# CPU_Board.net
KiCad netlist of a schematic drawn in Altium Designer
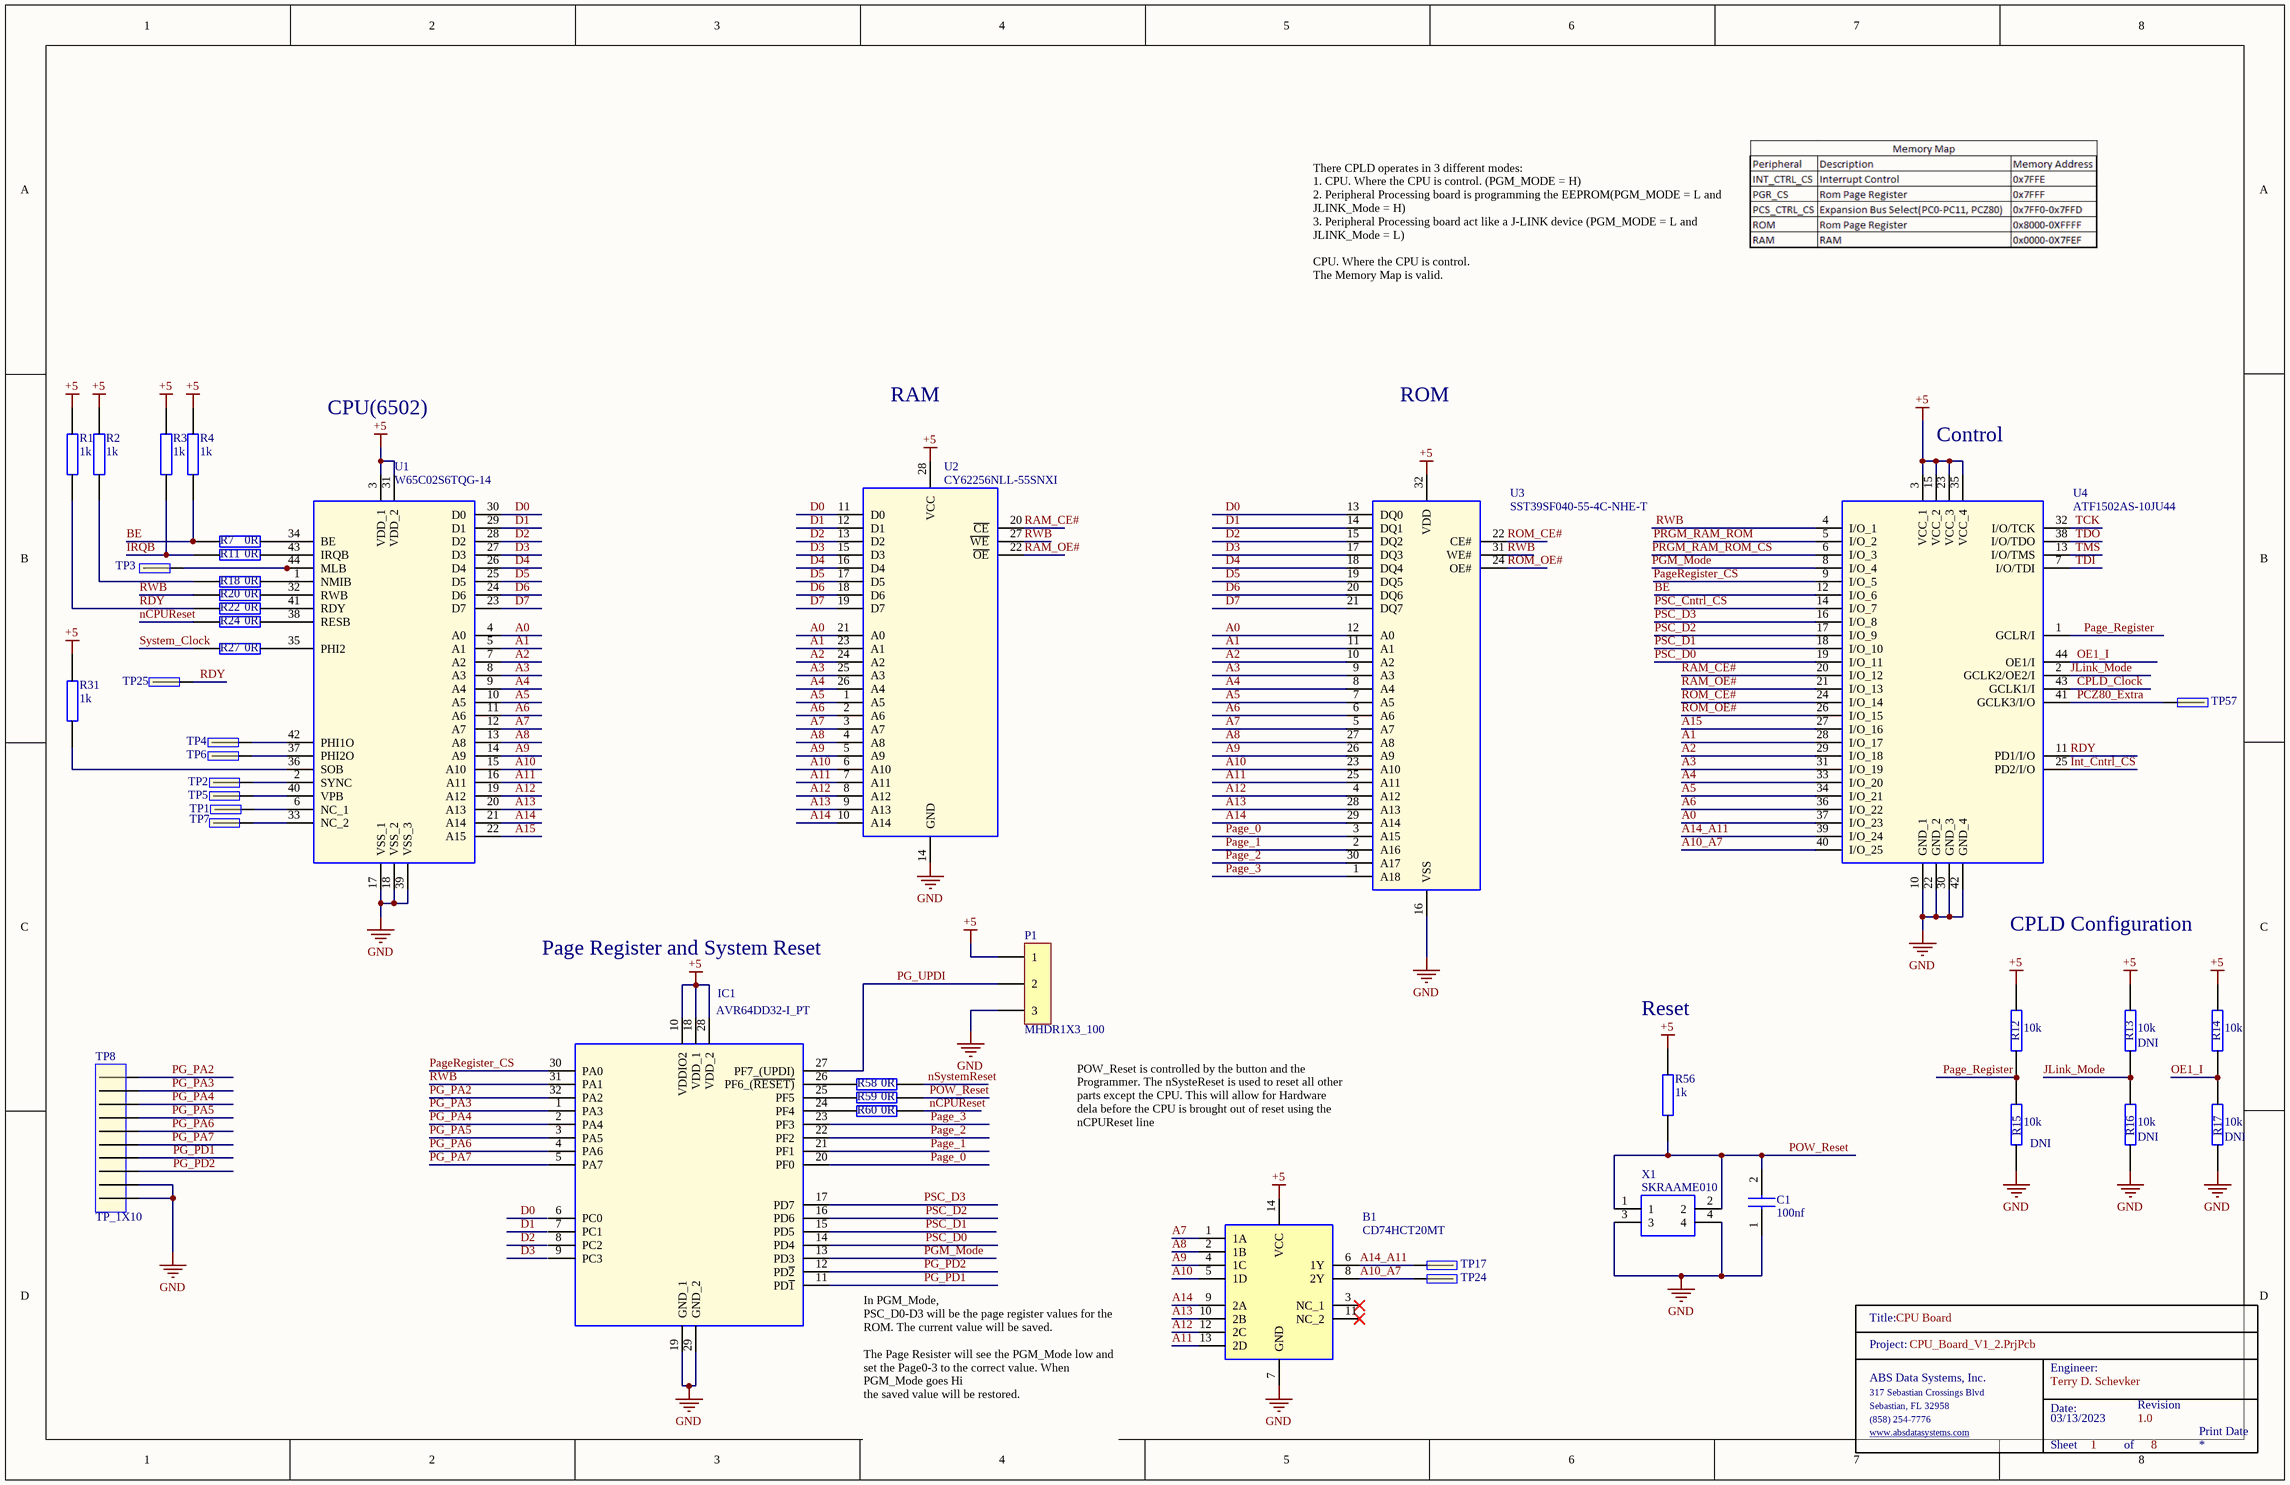
[diagram p0: CPU_Board.SchDoc]

(export (version "E")
  (design (tool "Eeschema 10.0.6"))
  (components
    (comp (ref "B1")
      (value "CD74HCT20MT")
      (footprint "SOIC127P600X175-14N")
      (description "Texas Instruments CD74HCT20MT, Dual 4-Input NAND Logic Gate, 14-Pin SOIC")
      (fields (field (name "MOUSER PART NUMBER") "595-CD74HCT20MT"))
      (libsource (lib "Logic") (part "CD74HCT20MT"))
    )
    (comp (ref "C1")
      (value "100nf")
      (footprint "0603")
      (description "Samsung Electro-Mechanics 0603 100nf")
      (libsource (lib "Capacitors") (part "CL10B104JB8NNNC"))
    )
    (comp (ref "IC1")
      (value "AVR64DD32-I_PT")
      (footprint "CPU_Memory:QFP80P900X900X120-32N")
      (description "Integrated Circuit")
      (fields (field (name "MANUFACTURER_PART_NUMBER") "AVR64DD32-I/PT ¦ MULTI-VOLTAGE I/O"))
      (libsource (lib "CPU_Memory") (part "AVR64DD32-I_PT"))
    )
    (comp (ref "P1")
      (value "MHDR1X3_100")
      (footprint "MHDR1X3_100")
      (description "Header, 3-Pin")
      (fields (field (name "PUBLISHER") "Altium Limited"))
      (libsource (lib "Connectors") (part "MHDR1X3_100"))
    )
    (comp (ref "R1")
      (value "1k")
      (footprint "0603")
      (description "YAGEO 0603 1k ohm")
      (fields
        (field (name "MOUSER PART NUMBER") "603-RC0603JR-070RL")
        (field (name "MANUFACTURER_PART_NUMBER") "RC0603JR-070RL")
      )
      (libsource (lib "Resistors") (part "AC0603FR-7W1KL"))
    )
    (comp (ref "R2")
      (value "1k")
      (footprint "0603")
      (description "YAGEO 0603 1k ohm")
      (fields
        (field (name "MOUSER PART NUMBER") "603-RC0603JR-070RL")
        (field (name "MANUFACTURER_PART_NUMBER") "RC0603JR-070RL")
      )
      (libsource (lib "Resistors") (part "AC0603FR-7W1KL"))
    )
    (comp (ref "R3")
      (value "1k")
      (footprint "0603")
      (description "YAGEO 0603 1k ohm")
      (fields
        (field (name "MOUSER PART NUMBER") "603-RC0603JR-070RL")
        (field (name "MANUFACTURER_PART_NUMBER") "RC0603JR-070RL")
      )
      (libsource (lib "Resistors") (part "AC0603FR-7W1KL"))
    )
    (comp (ref "R4")
      (value "1k")
      (footprint "0603")
      (description "YAGEO 0603 1k ohm")
      (fields
        (field (name "MOUSER PART NUMBER") "603-RC0603JR-070RL")
        (field (name "MANUFACTURER_PART_NUMBER") "RC0603JR-070RL")
      )
      (libsource (lib "Resistors") (part "AC0603FR-7W1KL"))
    )
    (comp (ref "R7")
      (value "0R")
      (footprint "0603")
      (description "YAGEO 0603 0 ohm")
      (fields
        (field (name "MOUSER PART NUMBER") "603-RC0603JR-070RL")
        (field (name "MANUFACTURER_PART_NUMBER") "RC0603JR-070RL")
      )
      (libsource (lib "Resistors") (part "RC0603JR-070RL"))
    )
    (comp (ref "R11")
      (value "0R")
      (footprint "0603")
      (description "YAGEO 0603 0 ohm")
      (fields
        (field (name "MOUSER PART NUMBER") "603-RC0603JR-070RL")
        (field (name "MANUFACTURER_PART_NUMBER") "RC0603JR-070RL")
      )
      (libsource (lib "Resistors") (part "RC0603JR-070RL"))
    )
    (comp (ref "R12")
      (value "10k")
      (footprint "0603")
      (description "YAGEO 0603 10k ohm")
      (fields
        (field (name "MOUSER PART NUMBER") "603-RC0603JR-070RL")
        (field (name "MANUFACTURER_PART_NUMBER") "RC0603JR-070RL")
      )
      (libsource (lib "Resistors") (part "RC0603JR-0710KL"))
    )
    (comp (ref "R13")
      (value "10k")
      (footprint "0603")
      (description "YAGEO 0603 10k ohm")
      (fields
        (field (name "MOUSER PART NUMBER") "603-RC0603JR-070RL")
        (field (name "MANUFACTURER_PART_NUMBER") "RC0603JR-070RL")
      )
      (libsource (lib "Resistors") (part "RC0603JR-0710KL"))
    )
    (comp (ref "R14")
      (value "10k")
      (footprint "0603")
      (description "YAGEO 0603 10k ohm")
      (fields
        (field (name "MOUSER PART NUMBER") "603-RC0603JR-070RL")
        (field (name "MANUFACTURER_PART_NUMBER") "RC0603JR-070RL")
      )
      (libsource (lib "Resistors") (part "RC0603JR-0710KL"))
    )
    (comp (ref "R15")
      (value "10k")
      (footprint "0603")
      (description "YAGEO 0603 10k ohm")
      (fields
        (field (name "MOUSER PART NUMBER") "603-RC0603JR-070RL")
        (field (name "MANUFACTURER_PART_NUMBER") "RC0603JR-070RL")
      )
      (libsource (lib "Resistors") (part "RC0603JR-0710KL"))
    )
    (comp (ref "R16")
      (value "10k")
      (footprint "0603")
      (description "YAGEO 0603 10k ohm")
      (fields
        (field (name "MOUSER PART NUMBER") "603-RC0603JR-070RL")
        (field (name "MANUFACTURER_PART_NUMBER") "RC0603JR-070RL")
      )
      (libsource (lib "Resistors") (part "RC0603JR-0710KL"))
    )
    (comp (ref "R17")
      (value "10k")
      (footprint "0603")
      (description "YAGEO 0603 10k ohm")
      (fields
        (field (name "MOUSER PART NUMBER") "603-RC0603JR-070RL")
        (field (name "MANUFACTURER_PART_NUMBER") "RC0603JR-070RL")
      )
      (libsource (lib "Resistors") (part "RC0603JR-0710KL"))
    )
    (comp (ref "R18")
      (value "0R")
      (footprint "0603")
      (description "YAGEO 0603 0 ohm")
      (fields
        (field (name "MOUSER PART NUMBER") "603-RC0603JR-070RL")
        (field (name "MANUFACTURER_PART_NUMBER") "RC0603JR-070RL")
      )
      (libsource (lib "Resistors") (part "RC0603JR-070RL"))
    )
    (comp (ref "R20")
      (value "0R")
      (footprint "0603")
      (description "YAGEO 0603 0 ohm")
      (fields
        (field (name "MOUSER PART NUMBER") "603-RC0603JR-070RL")
        (field (name "MANUFACTURER_PART_NUMBER") "RC0603JR-070RL")
      )
      (libsource (lib "Resistors") (part "RC0603JR-070RL"))
    )
    (comp (ref "R22")
      (value "0R")
      (footprint "0603")
      (description "YAGEO 0603 0 ohm")
      (fields
        (field (name "MOUSER PART NUMBER") "603-RC0603JR-070RL")
        (field (name "MANUFACTURER_PART_NUMBER") "RC0603JR-070RL")
      )
      (libsource (lib "Resistors") (part "RC0603JR-070RL"))
    )
    (comp (ref "R24")
      (value "0R")
      (footprint "0603")
      (description "YAGEO 0603 0 ohm")
      (fields
        (field (name "MOUSER PART NUMBER") "603-RC0603JR-070RL")
        (field (name "MANUFACTURER_PART_NUMBER") "RC0603JR-070RL")
      )
      (libsource (lib "Resistors") (part "RC0603JR-070RL"))
    )
    (comp (ref "R27")
      (value "0R")
      (footprint "0603")
      (description "YAGEO 0603 0 ohm")
      (fields
        (field (name "MOUSER PART NUMBER") "603-RC0603JR-070RL")
        (field (name "MANUFACTURER_PART_NUMBER") "RC0603JR-070RL")
      )
      (libsource (lib "Resistors") (part "RC0603JR-070RL"))
    )
    (comp (ref "R31")
      (value "1k")
      (footprint "Capacitors:0603")
      (description "YAGEO 0603 1k ohm")
      (fields
        (field (name "MOUSER PART NUMBER") "603-RC0603JR-070RL")
        (field (name "MANUFACTURER_PART_NUMBER") "RC0603JR-070RL")
      )
      (libsource (lib "Resistors") (part "AC0603FR-7W1KL"))
    )
    (comp (ref "R56")
      (value "1k")
      (footprint "0603")
      (description "YAGEO 0603 1k ohm")
      (fields
        (field (name "MOUSER PART NUMBER") "603-RC0603JR-070RL")
        (field (name "MANUFACTURER_PART_NUMBER") "RC0603JR-070RL")
      )
      (libsource (lib "Resistors") (part "AC0603FR-7W1KL"))
    )
    (comp (ref "R58")
      (value "0R")
      (footprint "Capacitors:0603")
      (description "YAGEO 0603 0 ohm")
      (fields
        (field (name "MOUSER PART NUMBER") "603-RC0603JR-070RL")
        (field (name "MANUFACTURER_PART_NUMBER") "RC0603JR-070RL")
      )
      (libsource (lib "Resistors") (part "RC0603JR-070RL"))
    )
    (comp (ref "R59")
      (value "0R")
      (footprint "0603")
      (description "YAGEO 0603 0 ohm")
      (fields
        (field (name "MOUSER PART NUMBER") "603-RC0603JR-070RL")
        (field (name "MANUFACTURER_PART_NUMBER") "RC0603JR-070RL")
      )
      (libsource (lib "Resistors") (part "RC0603JR-070RL"))
    )
    (comp (ref "R60")
      (value "0R")
      (footprint "0603")
      (description "YAGEO 0603 0 ohm")
      (fields
        (field (name "MOUSER PART NUMBER") "603-RC0603JR-070RL")
        (field (name "MANUFACTURER_PART_NUMBER") "RC0603JR-070RL")
      )
      (libsource (lib "Resistors") (part "RC0603JR-070RL"))
    )
    (comp (ref "TitleBlock_1") (value "TitleBlock") (libsource (lib "Misc") (part "TitleBlock")))
    (comp (ref "TP1")
      (value "TP")
      (footprint "TP")
      (fields
        (field (name "MANUFACTURER") "Samtec")
        (field (name "MANUFACTURER PART NUMBER") "TST-105-01-G-D")
      )
      (libsource (lib "Misc") (part "TP"))
    )
    (comp (ref "TP2")
      (value "TP")
      (footprint "TP")
      (fields
        (field (name "MANUFACTURER") "Samtec")
        (field (name "MANUFACTURER PART NUMBER") "TST-105-01-G-D")
      )
      (libsource (lib "Misc") (part "TP"))
    )
    (comp (ref "TP3")
      (value "TP")
      (footprint "TP")
      (fields
        (field (name "MANUFACTURER") "Samtec")
        (field (name "MANUFACTURER PART NUMBER") "TST-105-01-G-D")
      )
      (libsource (lib "Misc") (part "TP"))
    )
    (comp (ref "TP4")
      (value "TP")
      (footprint "TP")
      (fields
        (field (name "MANUFACTURER") "Samtec")
        (field (name "MANUFACTURER PART NUMBER") "TST-105-01-G-D")
      )
      (libsource (lib "Misc") (part "TP"))
    )
    (comp (ref "TP5")
      (value "TP")
      (footprint "TP")
      (fields
        (field (name "MANUFACTURER") "Samtec")
        (field (name "MANUFACTURER PART NUMBER") "TST-105-01-G-D")
      )
      (libsource (lib "Misc") (part "TP"))
    )
    (comp (ref "TP6")
      (value "TP")
      (footprint "TP")
      (fields
        (field (name "MANUFACTURER") "Samtec")
        (field (name "MANUFACTURER PART NUMBER") "TST-105-01-G-D")
      )
      (libsource (lib "Misc") (part "TP"))
    )
    (comp (ref "TP7")
      (value "TP")
      (footprint "TP")
      (fields
        (field (name "MANUFACTURER") "Samtec")
        (field (name "MANUFACTURER PART NUMBER") "TST-105-01-G-D")
      )
      (libsource (lib "Misc") (part "TP"))
    )
    (comp (ref "TP8")
      (value "TP_1X10")
      (footprint "TP_1X10")
      (fields
        (field (name "MANUFACTURER") "Samtec")
        (field (name "MANUFACTURER PART NUMBER") "TST-105-01-G-D")
      )
      (libsource (lib "Misc") (part "TP_1X10"))
    )
    (comp (ref "TP17")
      (value "TP")
      (footprint "TP")
      (fields
        (field (name "MANUFACTURER") "Samtec")
        (field (name "MANUFACTURER PART NUMBER") "TST-105-01-G-D")
      )
      (libsource (lib "") (part "TP_1"))
    )
    (comp (ref "TP24")
      (value "TP")
      (footprint "TP")
      (fields
        (field (name "MANUFACTURER") "Samtec")
        (field (name "MANUFACTURER PART NUMBER") "TST-105-01-G-D")
      )
      (libsource (lib "") (part "TP_1"))
    )
    (comp (ref "TP25")
      (value "TP")
      (footprint "TP")
      (fields
        (field (name "MANUFACTURER") "Samtec")
        (field (name "MANUFACTURER PART NUMBER") "TST-105-01-G-D")
      )
      (libsource (lib "Misc") (part "TP"))
    )
    (comp (ref "TP57")
      (value "TP")
      (footprint "TP")
      (fields
        (field (name "MANUFACTURER") "Samtec")
        (field (name "MANUFACTURER PART NUMBER") "TST-105-01-G-D")
      )
      (libsource (lib "") (part "TP_1"))
    )
    (comp (ref "U1")
      (value "W65C02S6TQG-14")
      (footprint "QFP-44")
      (description "Microprocessors - MPU 8-bit Microprocessor")
      (fields (field (name "MOUSER PART NUMBER") "955-W65C02S6TQG-14"))
      (libsource (lib "CPU_Memory") (part "W65C02S6TQG-14"))
    )
    (comp (ref "U2")
      (value "CY62256NLL-55SNXI")
      (footprint "SOP-28")
      (description "SRAM 256K 32K x 8 4.5-5.5V 28pin 330mil SOP Industrial (-40 85 C) Low Power Asynch")
      (fields (field (name "MOUSER PART NUMBER") "913-CY62256NLL55SNXI"))
      (libsource (lib "CPU_Memory") (part "CY62256NLL-55SNXI"))
    )
    (comp (ref "U3")
      (value "SST39SF040-55-4C-NHE-T")
      (footprint "CPU_Memory:plcc-32")
      (description "NOR Flash 4.5 to 5.5 1Mbit Multi-Purpose Flash")
      (fields (field (name "MOUSER PART NUMBER") "579-39SF040554CNHET"))
      (libsource (lib "CPU_Memory") (part "SST39SF040-55-4C-NHE-T"))
    )
    (comp (ref "U4")
      (value "ATF1502AS-10JU44")
      (footprint "PLCC-44N")
      (fields (field (name "MOUSER PART NUMBER") "556-AF1502AS10JU44"))
      (libsource (lib "Logic") (part "ATF1502AS-10JU44"))
    )
    (comp (ref "X1")
      (value "SKRAAME010")
      (footprint "SKRAAME010")
      (description "ALPS - SKRAAME010 - SWITCH, SMD, 1.96N, 6.2X6.2MM")
      (fields (field (name "MOUSER PART NUMBER") "688-SKRAAME010"))
      (libsource (lib "Misc") (part "SKRAAME010"))
    )
  )
  (nets
    (net (code "1") (name "+5") (class "Default")
      (node (ref "B1") (pin "14") (pinfunction "VCC_14") (pintype "passive"))
      (node (ref "IC1") (pin "10") (pinfunction "VDDIO2_10") (pintype "passive"))
      (node (ref "IC1") (pin "18") (pinfunction "VDD_1_18") (pintype "passive"))
      (node (ref "IC1") (pin "28") (pinfunction "VDD_2_28") (pintype "passive"))
      (node (ref "P1") (pin "1") (pinfunction "1_1") (pintype "passive"))
      (node (ref "R1") (pin "2") (pinfunction "2_2") (pintype "passive"))
      (node (ref "R12") (pin "1") (pinfunction "1_1") (pintype "passive"))
      (node (ref "R13") (pin "1") (pinfunction "1_1") (pintype "passive"))
      (node (ref "R14") (pin "1") (pinfunction "1_1") (pintype "passive"))
      (node (ref "R2") (pin "2") (pinfunction "2_2") (pintype "passive"))
      (node (ref "R3") (pin "2") (pinfunction "2_2") (pintype "passive"))
      (node (ref "R31") (pin "2") (pinfunction "2_2") (pintype "passive"))
      (node (ref "R4") (pin "2") (pinfunction "2_2") (pintype "passive"))
      (node (ref "R56") (pin "1") (pinfunction "1_1") (pintype "passive"))
      (node (ref "U1") (pin "3") (pinfunction "VDD_1_3") (pintype "passive"))
      (node (ref "U1") (pin "31") (pinfunction "VDD_2_31") (pintype "passive"))
      (node (ref "U2") (pin "28") (pinfunction "VCC_28") (pintype "passive"))
      (node (ref "U3") (pin "32") (pinfunction "VDD_32") (pintype "passive"))
      (node (ref "U4") (pin "15") (pinfunction "VCC_2_15") (pintype "passive"))
      (node (ref "U4") (pin "23") (pinfunction "VCC_3_23") (pintype "passive"))
      (node (ref "U4") (pin "3") (pinfunction "VCC_1_3") (pintype "passive"))
      (node (ref "U4") (pin "35") (pinfunction "VCC_4_35") (pintype "passive"))
    )
    (net (code "2") (name "/A0") (class "Default")
      (node (ref "U1") (pin "4") (pinfunction "A0_4") (pintype "passive"))
      (node (ref "U2") (pin "21") (pinfunction "A0_21") (pintype "passive"))
      (node (ref "U3") (pin "12") (pinfunction "A0_12") (pintype "passive"))
      (node (ref "U4") (pin "37") (pinfunction "I/O_23_37") (pintype "passive"))
    )
    (net (code "3") (name "/A1") (class "Default")
      (node (ref "U1") (pin "5") (pinfunction "A1_5") (pintype "passive"))
      (node (ref "U2") (pin "23") (pinfunction "A1_23") (pintype "passive"))
      (node (ref "U3") (pin "11") (pinfunction "A1_11") (pintype "passive"))
      (node (ref "U4") (pin "28") (pinfunction "I/O_17_28") (pintype "passive"))
    )
    (net (code "4") (name "/A2") (class "Default")
      (node (ref "U1") (pin "7") (pinfunction "A2_7") (pintype "passive"))
      (node (ref "U2") (pin "24") (pinfunction "A2_24") (pintype "passive"))
      (node (ref "U3") (pin "10") (pinfunction "A2_10") (pintype "passive"))
      (node (ref "U4") (pin "29") (pinfunction "I/O_18_29") (pintype "passive"))
    )
    (net (code "5") (name "/A3") (class "Default")
      (node (ref "U1") (pin "8") (pinfunction "A3_8") (pintype "passive"))
      (node (ref "U2") (pin "25") (pinfunction "A3_25") (pintype "passive"))
      (node (ref "U3") (pin "9") (pinfunction "A3_9") (pintype "passive"))
      (node (ref "U4") (pin "31") (pinfunction "I/O_19_31") (pintype "passive"))
    )
    (net (code "6") (name "/A4") (class "Default")
      (node (ref "U1") (pin "9") (pinfunction "A4_9") (pintype "passive"))
      (node (ref "U2") (pin "26") (pinfunction "A4_26") (pintype "passive"))
      (node (ref "U3") (pin "8") (pinfunction "A4_8") (pintype "passive"))
      (node (ref "U4") (pin "33") (pinfunction "I/O_20_33") (pintype "passive"))
    )
    (net (code "7") (name "/A5") (class "Default")
      (node (ref "U1") (pin "10") (pinfunction "A5_10") (pintype "passive"))
      (node (ref "U2") (pin "1") (pinfunction "A5_1") (pintype "passive"))
      (node (ref "U3") (pin "7") (pinfunction "A5_7") (pintype "passive"))
      (node (ref "U4") (pin "34") (pinfunction "I/O_21_34") (pintype "passive"))
    )
    (net (code "8") (name "/A6") (class "Default")
      (node (ref "U1") (pin "11") (pinfunction "A6_11") (pintype "passive"))
      (node (ref "U2") (pin "2") (pinfunction "A6_2") (pintype "passive"))
      (node (ref "U3") (pin "6") (pinfunction "A6_6") (pintype "passive"))
      (node (ref "U4") (pin "36") (pinfunction "I/O_22_36") (pintype "passive"))
    )
    (net (code "9") (name "/A7") (class "Default")
      (node (ref "B1") (pin "1") (pinfunction "1A_1") (pintype "passive"))
      (node (ref "U1") (pin "12") (pinfunction "A7_12") (pintype "passive"))
      (node (ref "U2") (pin "3") (pinfunction "A7_3") (pintype "passive"))
      (node (ref "U3") (pin "5") (pinfunction "A7_5") (pintype "passive"))
    )
    (net (code "10") (name "/A8") (class "Default")
      (node (ref "B1") (pin "2") (pinfunction "1B_2") (pintype "passive"))
      (node (ref "U1") (pin "13") (pinfunction "A8_13") (pintype "passive"))
      (node (ref "U2") (pin "4") (pinfunction "A8_4") (pintype "passive"))
      (node (ref "U3") (pin "27") (pinfunction "A8_27") (pintype "passive"))
    )
    (net (code "11") (name "/A9") (class "Default")
      (node (ref "B1") (pin "4") (pinfunction "1C_4") (pintype "passive"))
      (node (ref "U1") (pin "14") (pinfunction "A9_14") (pintype "passive"))
      (node (ref "U2") (pin "5") (pinfunction "A9_5") (pintype "passive"))
      (node (ref "U3") (pin "26") (pinfunction "A9_26") (pintype "passive"))
    )
    (net (code "12") (name "/A10") (class "Default")
      (node (ref "B1") (pin "5") (pinfunction "1D_5") (pintype "passive"))
      (node (ref "U1") (pin "15") (pinfunction "A10_15") (pintype "passive"))
      (node (ref "U2") (pin "6") (pinfunction "A10_6") (pintype "passive"))
      (node (ref "U3") (pin "23") (pinfunction "A10_23") (pintype "passive"))
    )
    (net (code "13") (name "/A10_A7") (class "Default")
      (node (ref "B1") (pin "8") (pinfunction "2Y_8") (pintype "passive"))
      (node (ref "TP24") (pin "1") (pinfunction "1_1") (pintype "passive"))
      (node (ref "U4") (pin "40") (pinfunction "I/O_25_40") (pintype "passive"))
    )
    (net (code "14") (name "/A11") (class "Default")
      (node (ref "B1") (pin "13") (pinfunction "2D_13") (pintype "passive"))
      (node (ref "U1") (pin "16") (pinfunction "A11_16") (pintype "passive"))
      (node (ref "U2") (pin "7") (pinfunction "A11_7") (pintype "passive"))
      (node (ref "U3") (pin "25") (pinfunction "A11_25") (pintype "passive"))
    )
    (net (code "15") (name "/A12") (class "Default")
      (node (ref "B1") (pin "12") (pinfunction "2C_12") (pintype "passive"))
      (node (ref "U1") (pin "19") (pinfunction "A12_19") (pintype "passive"))
      (node (ref "U2") (pin "8") (pinfunction "A12_8") (pintype "passive"))
      (node (ref "U3") (pin "4") (pinfunction "A12_4") (pintype "passive"))
    )
    (net (code "16") (name "/A13") (class "Default")
      (node (ref "B1") (pin "10") (pinfunction "2B_10") (pintype "passive"))
      (node (ref "U1") (pin "20") (pinfunction "A13_20") (pintype "passive"))
      (node (ref "U2") (pin "9") (pinfunction "A13_9") (pintype "passive"))
      (node (ref "U3") (pin "28") (pinfunction "A13_28") (pintype "passive"))
    )
    (net (code "17") (name "/A14") (class "Default")
      (node (ref "B1") (pin "9") (pinfunction "2A_9") (pintype "passive"))
      (node (ref "U1") (pin "21") (pinfunction "A14_21") (pintype "passive"))
      (node (ref "U2") (pin "10") (pinfunction "A14_10") (pintype "passive"))
      (node (ref "U3") (pin "29") (pinfunction "A14_29") (pintype "passive"))
    )
    (net (code "18") (name "/A14_A11") (class "Default")
      (node (ref "B1") (pin "6") (pinfunction "1Y_6") (pintype "passive"))
      (node (ref "TP17") (pin "1") (pinfunction "1_1") (pintype "passive"))
      (node (ref "U4") (pin "39") (pinfunction "I/O_24_39") (pintype "passive"))
    )
    (net (code "19") (name "/A15") (class "Default")
      (node (ref "U1") (pin "22") (pinfunction "A15_22") (pintype "passive"))
      (node (ref "U4") (pin "27") (pinfunction "I/O_16_27") (pintype "passive"))
    )
    (net (code "20") (name "/BE") (class "Default")
      (node (ref "R4") (pin "1") (pinfunction "1_1") (pintype "passive"))
      (node (ref "R7") (pin "1") (pinfunction "1_1") (pintype "passive"))
      (node (ref "U4") (pin "12") (pinfunction "I/O_6_12") (pintype "passive"))
    )
    (net (code "21") (name "/CPLD_Clock") (class "Default")
      (node (ref "U4") (pin "43") (pinfunction "GCLK1/I_43") (pintype "passive"))
    )
    (net (code "22") (name "/D0") (class "Default")
      (node (ref "U1") (pin "30") (pinfunction "D0_30") (pintype "passive"))
      (node (ref "U2") (pin "11") (pinfunction "D0_11") (pintype "passive"))
      (node (ref "U3") (pin "13") (pinfunction "DQ0_13") (pintype "passive"))
    )
    (net (code "23") (name "/D1") (class "Default")
      (node (ref "U1") (pin "29") (pinfunction "D1_29") (pintype "passive"))
      (node (ref "U2") (pin "12") (pinfunction "D1_12") (pintype "passive"))
      (node (ref "U3") (pin "14") (pinfunction "DQ1_14") (pintype "passive"))
    )
    (net (code "24") (name "/D2") (class "Default")
      (node (ref "U1") (pin "28") (pinfunction "D2_28") (pintype "passive"))
      (node (ref "U2") (pin "13") (pinfunction "D2_13") (pintype "passive"))
      (node (ref "U3") (pin "15") (pinfunction "DQ2_15") (pintype "passive"))
    )
    (net (code "25") (name "/D3") (class "Default")
      (node (ref "U1") (pin "27") (pinfunction "D3_27") (pintype "passive"))
      (node (ref "U2") (pin "15") (pinfunction "D3_15") (pintype "passive"))
      (node (ref "U3") (pin "17") (pinfunction "DQ3_17") (pintype "passive"))
    )
    (net (code "26") (name "/D4") (class "Default")
      (node (ref "U1") (pin "26") (pinfunction "D4_26") (pintype "passive"))
      (node (ref "U2") (pin "16") (pinfunction "D4_16") (pintype "passive"))
      (node (ref "U3") (pin "18") (pinfunction "DQ4_18") (pintype "passive"))
    )
    (net (code "27") (name "/D5") (class "Default")
      (node (ref "U1") (pin "25") (pinfunction "D5_25") (pintype "passive"))
      (node (ref "U2") (pin "17") (pinfunction "D5_17") (pintype "passive"))
      (node (ref "U3") (pin "19") (pinfunction "DQ5_19") (pintype "passive"))
    )
    (net (code "28") (name "/D6") (class "Default")
      (node (ref "U1") (pin "24") (pinfunction "D6_24") (pintype "passive"))
      (node (ref "U2") (pin "18") (pinfunction "D6_18") (pintype "passive"))
      (node (ref "U3") (pin "20") (pinfunction "DQ6_20") (pintype "passive"))
    )
    (net (code "29") (name "/D7") (class "Default")
      (node (ref "U1") (pin "23") (pinfunction "D7_23") (pintype "passive"))
      (node (ref "U2") (pin "19") (pinfunction "D7_19") (pintype "passive"))
      (node (ref "U3") (pin "21") (pinfunction "DQ7_21") (pintype "passive"))
    )
    (net (code "30") (name "/IRQB") (class "Default")
      (node (ref "R11") (pin "1") (pinfunction "1_1") (pintype "passive"))
      (node (ref "R3") (pin "1") (pinfunction "1_1") (pintype "passive"))
    )
    (net (code "31") (name "/Int_Cntrl_CS") (class "Default")
      (node (ref "U4") (pin "25") (pinfunction "PD2/I/O_25") (pintype "passive"))
    )
    (net (code "32") (name "/JLink_Mode") (class "Default")
      (node (ref "R13") (pin "2") (pinfunction "2_2") (pintype "passive"))
      (node (ref "R16") (pin "1") (pinfunction "1_1") (pintype "passive"))
      (node (ref "U4") (pin "2") (pinfunction "GCLK2/OE2/I_2") (pintype "passive"))
    )
    (net (code "33") (name "/OE1_I") (class "Default")
      (node (ref "R14") (pin "2") (pinfunction "2_2") (pintype "passive"))
      (node (ref "R17") (pin "1") (pinfunction "1_1") (pintype "passive"))
      (node (ref "U4") (pin "44") (pinfunction "OE1/I_44") (pintype "passive"))
    )
    (net (code "34") (name "/PCZ80_Extra") (class "Default")
      (node (ref "TP57") (pin "1") (pinfunction "1_1") (pintype "passive"))
      (node (ref "U4") (pin "41") (pinfunction "GCLK3/I/O_41") (pintype "passive"))
    )
    (net (code "35") (name "/PGM_Mode") (class "Default")
      (node (ref "IC1") (pin "13") (pinfunction "PD3_13") (pintype "passive"))
      (node (ref "U4") (pin "8") (pinfunction "I/O_4_8") (pintype "passive"))
    )
    (net (code "36") (name "/PG_PA2") (class "Default")
      (node (ref "IC1") (pin "32") (pinfunction "PA2_32") (pintype "passive"))
      (node (ref "TP8") (pin "1") (pinfunction "1_1") (pintype "passive"))
    )
    (net (code "37") (name "/PG_PA3") (class "Default")
      (node (ref "IC1") (pin "1") (pinfunction "PA3_1") (pintype "passive"))
      (node (ref "TP8") (pin "2") (pinfunction "2_2") (pintype "passive"))
    )
    (net (code "38") (name "/PG_PA4") (class "Default")
      (node (ref "IC1") (pin "2") (pinfunction "PA4_2") (pintype "passive"))
      (node (ref "TP8") (pin "3") (pinfunction "3_3") (pintype "passive"))
    )
    (net (code "39") (name "/PG_PA5") (class "Default")
      (node (ref "IC1") (pin "3") (pinfunction "PA5_3") (pintype "passive"))
      (node (ref "TP8") (pin "4") (pinfunction "4_4") (pintype "passive"))
    )
    (net (code "40") (name "/PG_PA6") (class "Default")
      (node (ref "IC1") (pin "4") (pinfunction "PA6_4") (pintype "passive"))
      (node (ref "TP8") (pin "5") (pinfunction "5_5") (pintype "passive"))
    )
    (net (code "41") (name "/PG_PA7") (class "Default")
      (node (ref "IC1") (pin "5") (pinfunction "PA7_5") (pintype "passive"))
      (node (ref "TP8") (pin "6") (pinfunction "6_6") (pintype "passive"))
    )
    (net (code "42") (name "/PG_PD1") (class "Default")
      (node (ref "IC1") (pin "11") (pinfunction "PD~{1}_11") (pintype "passive"))
      (node (ref "TP8") (pin "7") (pinfunction "7_7") (pintype "passive"))
    )
    (net (code "43") (name "/PG_PD2") (class "Default")
      (node (ref "IC1") (pin "12") (pinfunction "PD~{2}_12") (pintype "passive"))
      (node (ref "TP8") (pin "8") (pinfunction "8_8") (pintype "passive"))
    )
    (net (code "44") (name "/PG_UPDI") (class "Default")
      (node (ref "IC1") (pin "27") (pinfunction "PF7_(UPDI)_27") (pintype "passive"))
      (node (ref "P1") (pin "2") (pinfunction "2_2") (pintype "passive"))
    )
    (net (code "45") (name "/POW_Reset") (class "Default")
      (node (ref "C1") (pin "2") (pinfunction "2_2") (pintype "passive"))
      (node (ref "R56") (pin "2") (pinfunction "2_2") (pintype "passive"))
      (node (ref "R59") (pin "2") (pinfunction "2_2") (pintype "passive"))
      (node (ref "X1") (pin "1") (pinfunction "1_1") (pintype "passive"))
      (node (ref "X1") (pin "2") (pinfunction "2_2") (pintype "passive"))
    )
    (net (code "46") (name "/PRGM_RAM_ROM") (class "Default")
      (node (ref "U4") (pin "5") (pinfunction "I/O_2_5") (pintype "passive"))
    )
    (net (code "47") (name "/PRGM_RAM_ROM_CS") (class "Default")
      (node (ref "U4") (pin "6") (pinfunction "I/O_3_6") (pintype "passive"))
    )
    (net (code "48") (name "/PSC_Cntrl_CS") (class "Default")
      (node (ref "U4") (pin "14") (pinfunction "I/O_7_14") (pintype "passive"))
    )
    (net (code "49") (name "/PSC_D0") (class "Default")
      (node (ref "IC1") (pin "14") (pinfunction "PD4_14") (pintype "passive"))
      (node (ref "U4") (pin "19") (pinfunction "I/O_11_19") (pintype "passive"))
    )
    (net (code "50") (name "/PSC_D1") (class "Default")
      (node (ref "IC1") (pin "15") (pinfunction "PD5_15") (pintype "passive"))
      (node (ref "U4") (pin "18") (pinfunction "I/O_10_18") (pintype "passive"))
    )
    (net (code "51") (name "/PSC_D2") (class "Default")
      (node (ref "IC1") (pin "16") (pinfunction "PD6_16") (pintype "passive"))
      (node (ref "U4") (pin "17") (pinfunction "I/O_9_17") (pintype "passive"))
    )
    (net (code "52") (name "/PSC_D3") (class "Default")
      (node (ref "IC1") (pin "17") (pinfunction "PD7_17") (pintype "passive"))
      (node (ref "U4") (pin "16") (pinfunction "I/O_8_16") (pintype "passive"))
    )
    (net (code "53") (name "/PageRegister_CS") (class "Default")
      (node (ref "IC1") (pin "30") (pinfunction "PA0_30") (pintype "passive"))
      (node (ref "U4") (pin "9") (pinfunction "I/O_5_9") (pintype "passive"))
    )
    (net (code "54") (name "/Page_0") (class "Default")
      (node (ref "IC1") (pin "20") (pinfunction "PF0_20") (pintype "passive"))
      (node (ref "U3") (pin "3") (pinfunction "A15_3") (pintype "passive"))
    )
    (net (code "55") (name "/Page_1") (class "Default")
      (node (ref "IC1") (pin "21") (pinfunction "PF1_21") (pintype "passive"))
      (node (ref "U3") (pin "2") (pinfunction "A16_2") (pintype "passive"))
    )
    (net (code "56") (name "/Page_2") (class "Default")
      (node (ref "IC1") (pin "22") (pinfunction "PF2_22") (pintype "passive"))
      (node (ref "U3") (pin "30") (pinfunction "A17_30") (pintype "passive"))
    )
    (net (code "57") (name "/Page_3") (class "Default")
      (node (ref "IC1") (pin "23") (pinfunction "PF3_23") (pintype "passive"))
      (node (ref "U3") (pin "1") (pinfunction "A18_1") (pintype "passive"))
    )
    (net (code "58") (name "/Page_Register") (class "Default")
      (node (ref "R12") (pin "2") (pinfunction "2_2") (pintype "passive"))
      (node (ref "R15") (pin "1") (pinfunction "1_1") (pintype "passive"))
      (node (ref "U4") (pin "1") (pinfunction "GCLR/I_1") (pintype "passive"))
    )
    (net (code "59") (name "/RAM_CE#") (class "Default")
      (node (ref "U2") (pin "20") (pinfunction "CE_20") (pintype "passive"))
      (node (ref "U4") (pin "20") (pinfunction "I/O_12_20") (pintype "passive"))
    )
    (net (code "60") (name "/RAM_OE#") (class "Default")
      (node (ref "U2") (pin "22") (pinfunction "OE_22") (pintype "passive"))
      (node (ref "U4") (pin "21") (pinfunction "I/O_13_21") (pintype "passive"))
    )
    (net (code "61") (name "/RDY") (class "Default")
      (node (ref "R1") (pin "1") (pinfunction "1_1") (pintype "passive"))
      (node (ref "R22") (pin "1") (pinfunction "1_1") (pintype "passive"))
      (node (ref "TP25") (pin "1") (pinfunction "1_1") (pintype "passive"))
      (node (ref "U4") (pin "11") (pinfunction "PD1/I/O_11") (pintype "passive"))
    )
    (net (code "62") (name "/ROM_CE#") (class "Default")
      (node (ref "U3") (pin "22") (pinfunction "CE#_22") (pintype "passive"))
      (node (ref "U4") (pin "24") (pinfunction "I/O_14_24") (pintype "passive"))
    )
    (net (code "63") (name "/ROM_OE#") (class "Default")
      (node (ref "U3") (pin "24") (pinfunction "OE#_24") (pintype "passive"))
      (node (ref "U4") (pin "26") (pinfunction "I/O_15_26") (pintype "passive"))
    )
    (net (code "64") (name "/RWB") (class "Default")
      (node (ref "IC1") (pin "31") (pinfunction "PA1_31") (pintype "passive"))
      (node (ref "R20") (pin "1") (pinfunction "1_1") (pintype "passive"))
      (node (ref "U2") (pin "27") (pinfunction "WE_27") (pintype "passive"))
      (node (ref "U3") (pin "31") (pinfunction "WE#_31") (pintype "passive"))
      (node (ref "U4") (pin "4") (pinfunction "I/O_1_4") (pintype "passive"))
    )
    (net (code "65") (name "/System_Clock") (class "Default")
      (node (ref "R27") (pin "1") (pinfunction "1_1") (pintype "passive"))
    )
    (net (code "66") (name "/TCK") (class "Default")
      (node (ref "U4") (pin "32") (pinfunction "I/O/TCK_32") (pintype "passive"))
    )
    (net (code "67") (name "/TDI") (class "Default")
      (node (ref "U4") (pin "7") (pinfunction "I/O/TDI_7") (pintype "passive"))
    )
    (net (code "68") (name "/TDO") (class "Default")
      (node (ref "U4") (pin "38") (pinfunction "I/O/TDO_38") (pintype "passive"))
    )
    (net (code "69") (name "/TMS") (class "Default")
      (node (ref "U4") (pin "13") (pinfunction "I/O/TMS_13") (pintype "passive"))
    )
    (net (code "70") (name "/nCPUReset") (class "Default")
      (node (ref "R24") (pin "1") (pinfunction "1_1") (pintype "passive"))
      (node (ref "R60") (pin "2") (pinfunction "2_2") (pintype "passive"))
    )
    (net (code "71") (name "/nSystemReset") (class "Default")
      (node (ref "R58") (pin "2") (pinfunction "2_2") (pintype "passive"))
    )
    (net (code "72") (name "GND") (class "Default")
      (node (ref "B1") (pin "7") (pinfunction "GND_7") (pintype "passive"))
      (node (ref "C1") (pin "1") (pinfunction "1_1") (pintype "passive"))
      (node (ref "IC1") (pin "19") (pinfunction "GND_1_19") (pintype "passive"))
      (node (ref "IC1") (pin "29") (pinfunction "GND_2_29") (pintype "passive"))
      (node (ref "P1") (pin "3") (pinfunction "3_3") (pintype "passive"))
      (node (ref "R15") (pin "2") (pinfunction "2_2") (pintype "passive"))
      (node (ref "R16") (pin "2") (pinfunction "2_2") (pintype "passive"))
      (node (ref "R17") (pin "2") (pinfunction "2_2") (pintype "passive"))
      (node (ref "TP8") (pin "10") (pinfunction "10_10") (pintype "passive"))
      (node (ref "TP8") (pin "9") (pinfunction "9_9") (pintype "passive"))
      (node (ref "U1") (pin "17") (pinfunction "VSS_1_17") (pintype "passive"))
      (node (ref "U1") (pin "18") (pinfunction "VSS_2_18") (pintype "passive"))
      (node (ref "U1") (pin "39") (pinfunction "VSS_3_39") (pintype "passive"))
      (node (ref "U2") (pin "14") (pinfunction "GND_14") (pintype "passive"))
      (node (ref "U3") (pin "16") (pinfunction "VSS_16") (pintype "passive"))
      (node (ref "U4") (pin "10") (pinfunction "GND_1_10") (pintype "passive"))
      (node (ref "U4") (pin "22") (pinfunction "GND_2_22") (pintype "passive"))
      (node (ref "U4") (pin "30") (pinfunction "GND_3_30") (pintype "passive"))
      (node (ref "U4") (pin "42") (pinfunction "GND_4_42") (pintype "passive"))
      (node (ref "X1") (pin "3") (pinfunction "3_3") (pintype "passive"))
      (node (ref "X1") (pin "4") (pinfunction "4_4") (pintype "passive"))
    )
    (net (code "73") (name "Net-(IC1-PF4)") (class "Default")
      (node (ref "IC1") (pin "24") (pinfunction "PF4_24") (pintype "passive"))
      (node (ref "R60") (pin "1") (pinfunction "1_1") (pintype "passive"))
    )
    (net (code "74") (name "Net-(IC1-PF5)") (class "Default")
      (node (ref "IC1") (pin "25") (pinfunction "PF5_25") (pintype "passive"))
      (node (ref "R59") (pin "1") (pinfunction "1_1") (pintype "passive"))
    )
    (net (code "75") (name "Net-(IC1-PF6_(~{RESET)})") (class "Default")
      (node (ref "IC1") (pin "26") (pinfunction "PF6_(~{RESET)}_26") (pintype "passive"))
      (node (ref "R58") (pin "1") (pinfunction "1_1") (pintype "passive"))
    )
    (net (code "76") (name "Net-(R18-Pad1)") (class "Default")
      (node (ref "R18") (pin "1") (pinfunction "1_1") (pintype "passive"))
      (node (ref "R2") (pin "1") (pinfunction "1_1") (pintype "passive"))
    )
    (net (code "77") (name "Net-(U1-BE)") (class "Default")
      (node (ref "R7") (pin "2") (pinfunction "2_2") (pintype "passive"))
      (node (ref "U1") (pin "34") (pinfunction "BE_34") (pintype "passive"))
    )
    (net (code "78") (name "Net-(U1-IRQB)") (class "Default")
      (node (ref "R11") (pin "2") (pinfunction "2_2") (pintype "passive"))
      (node (ref "U1") (pin "43") (pinfunction "IRQB_43") (pintype "passive"))
    )
    (net (code "79") (name "Net-(U1-MLB)") (class "Default")
      (node (ref "TP3") (pin "1") (pinfunction "1_1") (pintype "passive"))
      (node (ref "U1") (pin "44") (pinfunction "MLB_44") (pintype "passive"))
    )
    (net (code "80") (name "Net-(U1-NC_1)") (class "Default")
      (node (ref "TP1") (pin "1") (pinfunction "1_1") (pintype "passive"))
      (node (ref "U1") (pin "6") (pinfunction "NC_1_6") (pintype "passive"))
    )
    (net (code "81") (name "Net-(U1-NC_2)") (class "Default")
      (node (ref "TP7") (pin "1") (pinfunction "1_1") (pintype "passive"))
      (node (ref "U1") (pin "33") (pinfunction "NC_2_33") (pintype "passive"))
    )
    (net (code "82") (name "Net-(U1-NMIB)") (class "Default")
      (node (ref "R18") (pin "2") (pinfunction "2_2") (pintype "passive"))
      (node (ref "U1") (pin "1") (pinfunction "NMIB_1") (pintype "passive"))
    )
    (net (code "83") (name "Net-(U1-PHI1O)") (class "Default")
      (node (ref "TP4") (pin "1") (pinfunction "1_1") (pintype "passive"))
      (node (ref "U1") (pin "42") (pinfunction "PHI1O_42") (pintype "passive"))
    )
    (net (code "84") (name "Net-(U1-PHI2)") (class "Default")
      (node (ref "R27") (pin "2") (pinfunction "2_2") (pintype "passive"))
      (node (ref "U1") (pin "35") (pinfunction "PHI2_35") (pintype "passive"))
    )
    (net (code "85") (name "Net-(U1-PHI2O)") (class "Default")
      (node (ref "TP6") (pin "1") (pinfunction "1_1") (pintype "passive"))
      (node (ref "U1") (pin "37") (pinfunction "PHI2O_37") (pintype "passive"))
    )
    (net (code "86") (name "Net-(U1-RDY)") (class "Default")
      (node (ref "R22") (pin "2") (pinfunction "2_2") (pintype "passive"))
      (node (ref "U1") (pin "41") (pinfunction "RDY_41") (pintype "passive"))
    )
    (net (code "87") (name "Net-(U1-RESB)") (class "Default")
      (node (ref "R24") (pin "2") (pinfunction "2_2") (pintype "passive"))
      (node (ref "U1") (pin "38") (pinfunction "RESB_38") (pintype "passive"))
    )
    (net (code "88") (name "Net-(U1-RWB)") (class "Default")
      (node (ref "R20") (pin "2") (pinfunction "2_2") (pintype "passive"))
      (node (ref "U1") (pin "32") (pinfunction "RWB_32") (pintype "passive"))
    )
    (net (code "89") (name "Net-(U1-SOB)") (class "Default")
      (node (ref "R31") (pin "1") (pinfunction "1_1") (pintype "passive"))
      (node (ref "U1") (pin "36") (pinfunction "SOB_36") (pintype "passive"))
    )
    (net (code "90") (name "Net-(U1-SYNC)") (class "Default")
      (node (ref "TP2") (pin "1") (pinfunction "1_1") (pintype "passive"))
      (node (ref "U1") (pin "2") (pinfunction "SYNC_2") (pintype "passive"))
    )
    (net (code "91") (name "Net-(U1-VPB)") (class "Default")
      (node (ref "TP5") (pin "1") (pinfunction "1_1") (pintype "passive"))
      (node (ref "U1") (pin "40") (pinfunction "VPB_40") (pintype "passive"))
    )
    (net (code "92") (name "unconnected-(B1-NC_1-Pad3)") (class "Default")
      (node (ref "B1") (pin "3") (pinfunction "NC_1_3") (pintype "passive+no_connect"))
    )
    (net (code "93") (name "unconnected-(B1-NC_2-Pad11)") (class "Default")
      (node (ref "B1") (pin "11") (pinfunction "NC_2_11") (pintype "passive+no_connect"))
    )
    (net (code "94") (name "unconnected-(IC1-PC0-Pad6)") (class "Default")
      (node (ref "IC1") (pin "6") (pinfunction "PC0_6") (pintype "passive"))
    )
    (net (code "95") (name "unconnected-(IC1-PC1-Pad7)") (class "Default")
      (node (ref "IC1") (pin "7") (pinfunction "PC1_7") (pintype "passive"))
    )
    (net (code "96") (name "unconnected-(IC1-PC2-Pad8)") (class "Default")
      (node (ref "IC1") (pin "8") (pinfunction "PC2_8") (pintype "passive"))
    )
    (net (code "97") (name "unconnected-(IC1-PC3-Pad9)") (class "Default")
      (node (ref "IC1") (pin "9") (pinfunction "PC3_9") (pintype "passive"))
    )
  )
)
